# MQ.net
KiCad netlist of a schematic drawn in Altium Designer
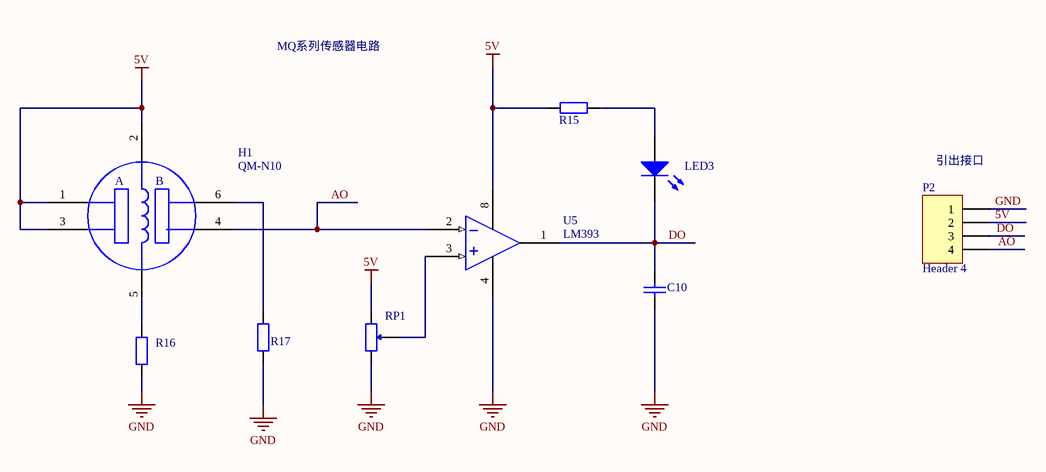
[diagram p0: MQ.SchDoc]

(export (version "E")
  (design (tool "Eeschema 10.0.6"))
  (components
    (comp (ref "C10")
      (value "104")
      (footprint "C0805_L")
      (description "贴片电容/MLCC电容")
      (libsource (lib "0.1 - 电阻-电容-电感-保险丝-晶振-晶体-磁珠-电位器-法拉电容-馈通电容") (part "C"))
    )
    (comp (ref "H1") (value "QM-N10") (libsource (lib "MQ-2") (part "QM-N10")))
    (comp (ref "LED3")
      (value "红色")
      (footprint "LED0805_G")
      (description "贴片LED")
      (libsource (lib "0.3 - LED发光二极管-IR二极管_接收管-光耦") (part "LED"))
    )
    (comp (ref "P2")
      (value "Header 4")
      (footprint "HDR1X4")
      (description "Header, 4-Pin")
      (fields (field (name "PUBLISHER") "Altium Limited"))
      (libsource (lib "Miscellaneous Connectors") (part "Header 4"))
    )
    (comp (ref "R15")
      (value "1K")
      (footprint "R0805_L")
      (description "贴片电阻")
      (libsource (lib "0.1 - 电阻-电容-电感-保险丝-晶振-晶体-磁珠-电位器-法拉电容-馈通电容") (part "R"))
    )
    (comp (ref "R16")
      (value "1K")
      (footprint "R0805_L")
      (description "贴片电阻")
      (libsource (lib "0.1 - 电阻-电容-电感-保险丝-晶振-晶体-磁珠-电位器-法拉电容-馈通电容") (part "R"))
    )
    (comp (ref "R17")
      (value "1K")
      (footprint "R0805_L")
      (description "贴片电阻")
      (libsource (lib "0.1 - 电阻-电容-电感-保险丝-晶振-晶体-磁珠-电位器-法拉电容-馈通电容") (part "R"))
    )
    (comp (ref "RP1")
      (value "10K")
      (footprint "3303W")
      (description "贴片电位器")
      (libsource (lib "0.1 - 电阻-电容-电感-保险丝-晶振-晶体-磁珠-电位器-法拉电容-馈通电容") (part "RP-SMD"))
    )
    (comp (ref "U5") (value "LM393") (libsource (lib "MQ-2") (part "LM393")))
  )
  (nets
    (net (code "1") (name "/AO") (class "Default")
      (node (ref "P2") (pin "4") (pinfunction "4_4") (pintype "passive"))
      (node (ref "U5") (pin "2") (pintype "input"))
    )
    (net (code "2") (name "/DO") (class "Default")
      (node (ref "C10") (pin "2") (pinfunction "2_2") (pintype "passive"))
      (node (ref "LED3") (pin "2") (pinfunction "K_2") (pintype "passive"))
      (node (ref "P2") (pin "3") (pinfunction "3_3") (pintype "passive"))
    )
    (net (code "3") (name "5V") (class "Default")
      (node (ref "P2") (pin "2") (pinfunction "2_2") (pintype "passive"))
      (node (ref "R15") (pin "2") (pinfunction "2_2") (pintype "passive"))
      (node (ref "RP1") (pin "1") (pinfunction "1_1") (pintype "passive"))
    )
    (net (code "4") (name "GND") (class "Default")
      (node (ref "C10") (pin "1") (pinfunction "1_1") (pintype "passive"))
      (node (ref "P2") (pin "1") (pinfunction "1_1") (pintype "passive"))
      (node (ref "R16") (pin "1") (pinfunction "1_1") (pintype "passive"))
      (node (ref "R17") (pin "1") (pinfunction "1_1") (pintype "passive"))
      (node (ref "RP1") (pin "3") (pinfunction "3_3") (pintype "passive"))
    )
    (net (code "5") (name "Net-(LED3-A)") (class "Default")
      (node (ref "LED3") (pin "1") (pinfunction "A_1") (pintype "passive"))
      (node (ref "R15") (pin "1") (pinfunction "1_1") (pintype "passive"))
    )
    (net (code "6") (name "Net-(RP1-Pad2)") (class "Default")
      (node (ref "RP1") (pin "2") (pinfunction "2_2") (pintype "passive"))
      (node (ref "U5") (pin "3") (pintype "input"))
    )
    (net (code "7") (name "unconnected-(H1-Pad1)") (class "Default")
      (node (ref "H1") (pin "1") (pintype "passive"))
    )
    (net (code "8") (name "unconnected-(H1-Pad2)") (class "Default")
      (node (ref "H1") (pin "2") (pintype "passive"))
    )
    (net (code "9") (name "unconnected-(H1-Pad3)") (class "Default")
      (node (ref "H1") (pin "3") (pintype "passive"))
    )
    (net (code "10") (name "unconnected-(H1-Pad4)") (class "Default")
      (node (ref "H1") (pin "4") (pintype "passive"))
    )
    (net (code "11") (name "unconnected-(H1-Pad5)") (class "Default")
      (node (ref "H1") (pin "5") (pintype "passive"))
    )
    (net (code "12") (name "unconnected-(H1-Pad6)") (class "Default")
      (node (ref "H1") (pin "6") (pintype "passive"))
    )
    (net (code "13") (name "unconnected-(R16-Pad2)") (class "Default")
      (node (ref "R16") (pin "2") (pinfunction "2_2") (pintype "passive"))
    )
    (net (code "14") (name "unconnected-(R17-Pad2)") (class "Default")
      (node (ref "R17") (pin "2") (pinfunction "2_2") (pintype "passive"))
    )
    (net (code "15") (name "unconnected-(U5-Pad1)") (class "Default")
      (node (ref "U5") (pin "1") (pintype "passive"))
    )
    (net (code "16") (name "unconnected-(U5-Pad4)") (class "Default")
      (node (ref "U5") (pin "4") (pintype "passive"))
    )
    (net (code "17") (name "unconnected-(U5-Pad8)") (class "Default")
      (node (ref "U5") (pin "8") (pintype "passive"))
    )
  )
)
